# V2_0.net
KiCad netlist of a schematic drawn in Altium Designer
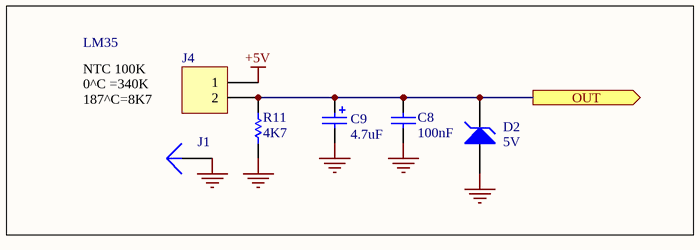
[diagram p0: V2.0.SchDoc]

(export (version "E")
  (design (tool "Eeschema 10.0.6"))
  (components
    (comp (ref "C8")
      (value "100nF")
      (footprint "CAPNTO2.54-3.05x1.78A")
      (description "Capacitor")
      (fields (field (name "MANUFACTURER") "Generic Components") (field (name "PUBLISHER") "Altium Limited"))
      (libsource (lib "Miscellaneous Devices") (part "Cap"))
    )
    (comp (ref "C9")
      (value "4.7uF")
      (footprint "CAPPR2.5-6.3x5")
      (description "Polarized Capacitor (Radial)")
      (fields (field (name "MANUFACTURER") "Generic Components") (field (name "PUBLISHER") "Altium Limited"))
      (libsource (lib "Miscellaneous Devices") (part "Cap Pol1"))
    )
    (comp (ref "D2")
      (value "5V")
      (footprint "DIODE0.4_Glass")
      (description "Zener Diode")
      (fields (field (name "MANUFACTURER") "Generic Components") (field (name "PUBLISHER") "Altium Limited"))
      (libsource (lib "Miscellaneous Devices") (part "D Zener"))
    )
    (comp (ref "J1")
      (value "COAX-M")
      (footprint "Fonics_1PIN_1")
      (description "Coax-M Connector")
      (fields (field (name "MANUFACTURER") "Generic Components") (field (name "PUBLISHER") "Altium Limited"))
      (libsource (lib "Miscellaneous Connectors") (part "COAX-M"))
    )
    (comp (ref "J4")
      (value "2PIN")
      (footprint "Fonics_2PIN_1")
      (description "Header, 2-Pin")
      (fields (field (name "PUBLISHER") "Altium Limited"))
      (libsource (lib "Miscellaneous Connectors") (part "Header 2"))
    )
    (comp (ref "R11")
      (value "4K7")
      (footprint "AXIAL-0.4")
      (description "Resistor")
      (fields (field (name "PUBLISHER") "Altium Limited"))
      (libsource (lib "Miscellaneous Devices") (part "Res1"))
    )
  )
  (nets
    (net (code "1") (name "+5V") (class "Default")
      (node (ref "J4") (pin "1") (pinfunction "1_1") (pintype "passive"))
    )
    (net (code "2") (name "/OUT") (class "Default")
      (node (ref "C8") (pin "2") (pinfunction "2_2") (pintype "passive"))
      (node (ref "C9") (pin "1") (pinfunction "1_1") (pintype "passive"))
      (node (ref "D2") (pin "2") (pinfunction "K_2") (pintype "passive"))
      (node (ref "J4") (pin "2") (pinfunction "2_2") (pintype "passive"))
      (node (ref "R11") (pin "1") (pinfunction "1_1") (pintype "passive"))
    )
    (net (code "3") (name "GND") (class "Default")
      (node (ref "C8") (pin "1") (pinfunction "1_1") (pintype "passive"))
      (node (ref "C9") (pin "2") (pinfunction "2_2") (pintype "passive"))
      (node (ref "D2") (pin "1") (pinfunction "A_1") (pintype "passive"))
      (node (ref "J1") (pin "1") (pinfunction "A_1") (pintype "passive"))
      (node (ref "R11") (pin "2") (pinfunction "2_2") (pintype "passive"))
    )
  )
)
